# Kasli-SOC_ETH_PHY.net
KiCad netlist of a schematic drawn in Altium Designer
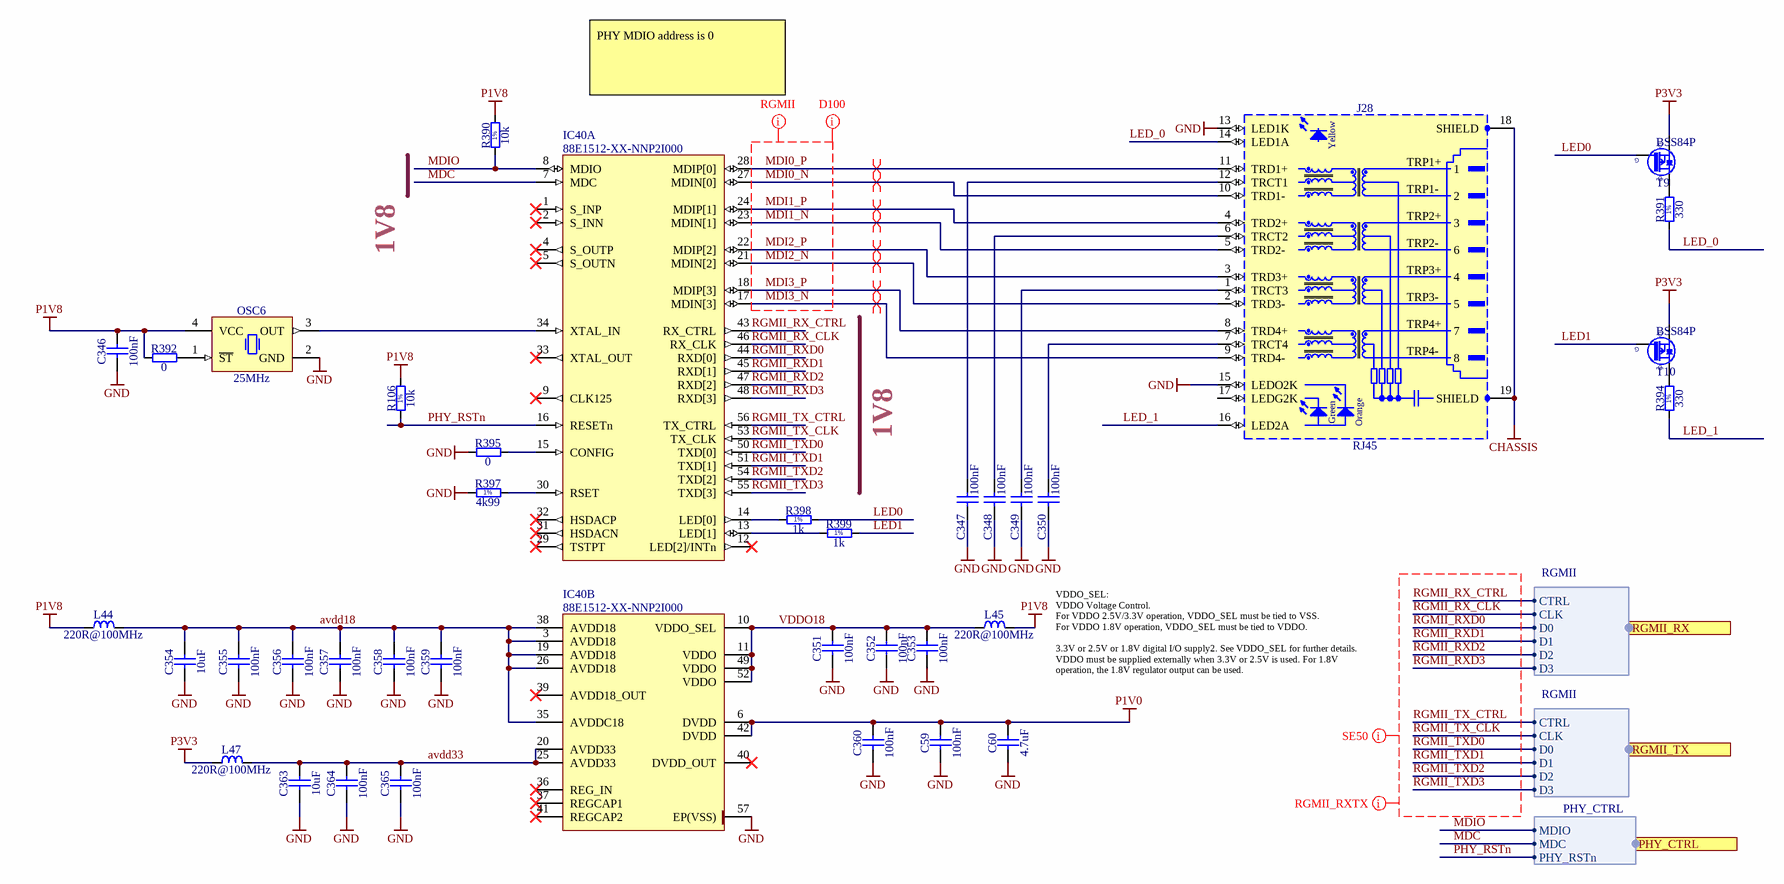
[diagram p0: Kasli-SOC_ETH_PHY.SchDoc]

(export (version "E")
  (design (tool "Eeschema 10.0.6"))
  (components
    (comp (ref "C59")
      (value "100nF")
      (footprint "CAPC0603X33N")
      (description "Non-polarised capacitor")
      (fields
        (field (name "PART NUMBER") "CC0201_100NF_6.3V_10%_X5R")
        (field (name "VOLTAGE") "6.3V")
        (field (name "AUTHOR") "CERN DEM JLC")
      )
      (libsource (lib "Capacitors") (part "Capacitor - non polarized"))
    )
    (comp (ref "C60")
      (value "4.7uF")
      (footprint "CAPC1709X95N")
      (description "Non-polarised capacitor")
      (fields
        (field (name "PART NUMBER") "CC0603_4.7UF_16V_10%_X5R")
        (field (name "VOLTAGE") "16V")
        (field (name "AUTHOR") "CERN DEM JLC")
      )
      (libsource (lib "Capacitors") (part "Capacitor - non polarized"))
    )
    (comp (ref "C346")
      (value "100nF")
      (footprint "CAPC1005X55N")
      (description "Non-polarised capacitor")
      (fields
        (field (name "PART NUMBER") "CC0402_100NF_16V_10%_X7R")
        (field (name "VOLTAGE") "16V")
        (field (name "AUTHOR") "CERN DEM JLC")
      )
      (libsource (lib "Capacitors") (part "Capacitor - non polarized"))
    )
    (comp (ref "C347")
      (value "100nF")
      (footprint "CAPC1005X55N")
      (description "Non-polarised capacitor")
      (fields
        (field (name "PART NUMBER") "CC0402_100NF_16V_10%_X7R")
        (field (name "VOLTAGE") "16V")
        (field (name "AUTHOR") "CERN DEM JLC")
      )
      (libsource (lib "Capacitors") (part "Capacitor - non polarized"))
    )
    (comp (ref "C348")
      (value "100nF")
      (footprint "CAPC1005X55N")
      (description "Non-polarised capacitor")
      (fields
        (field (name "PART NUMBER") "CC0402_100NF_16V_10%_X7R")
        (field (name "VOLTAGE") "16V")
        (field (name "AUTHOR") "CERN DEM JLC")
      )
      (libsource (lib "Capacitors") (part "Capacitor - non polarized"))
    )
    (comp (ref "C349")
      (value "100nF")
      (footprint "CAPC1005X55N")
      (description "Non-polarised capacitor")
      (fields
        (field (name "PART NUMBER") "CC0402_100NF_16V_10%_X7R")
        (field (name "VOLTAGE") "16V")
        (field (name "AUTHOR") "CERN DEM JLC")
      )
      (libsource (lib "Capacitors") (part "Capacitor - non polarized"))
    )
    (comp (ref "C350")
      (value "100nF")
      (footprint "CAPC1005X55N")
      (description "Non-polarised capacitor")
      (fields
        (field (name "PART NUMBER") "CC0402_100NF_16V_10%_X7R")
        (field (name "VOLTAGE") "16V")
        (field (name "AUTHOR") "CERN DEM JLC")
      )
      (libsource (lib "Capacitors") (part "Capacitor - non polarized"))
    )
    (comp (ref "C351")
      (value "100nF")
      (footprint "CAPC0603X33N")
      (description "Non-polarised capacitor")
      (fields
        (field (name "PART NUMBER") "CC0201_100NF_6.3V_10%_X5R")
        (field (name "VOLTAGE") "6.3V")
        (field (name "AUTHOR") "CERN DEM JLC")
      )
      (libsource (lib "Capacitors") (part "Capacitor - non polarized"))
    )
    (comp (ref "C352")
      (value "100nF")
      (footprint "CAPC0603X33N")
      (description "Non-polarised capacitor")
      (fields
        (field (name "PART NUMBER") "CC0201_100NF_6.3V_10%_X5R")
        (field (name "VOLTAGE") "6.3V")
        (field (name "AUTHOR") "CERN DEM JLC")
      )
      (libsource (lib "Capacitors") (part "Capacitor - non polarized"))
    )
    (comp (ref "C353")
      (value "100nF")
      (footprint "CAPC0603X33N")
      (description "Non-polarised capacitor")
      (fields
        (field (name "PART NUMBER") "CC0201_100NF_6.3V_10%_X5R")
        (field (name "VOLTAGE") "6.3V")
        (field (name "AUTHOR") "CERN DEM JLC")
      )
      (libsource (lib "Capacitors") (part "Capacitor - non polarized"))
    )
    (comp (ref "C354")
      (value "10uF")
      (footprint "CAPC1608X80N")
      (description "Non-polarised capacitor")
      (fields
        (field (name "PART NUMBER") "CC0603_10UF_16V_20%_X5R")
        (field (name "VOLTAGE") "16V")
        (field (name "AUTHOR") "CERN DEM MR")
      )
      (libsource (lib "Capacitors") (part "Capacitor - non polarized"))
    )
    (comp (ref "C355")
      (value "100nF")
      (footprint "CAPC0603X33N")
      (description "Non-polarised capacitor")
      (fields
        (field (name "PART NUMBER") "CC0201_100NF_6.3V_10%_X5R")
        (field (name "VOLTAGE") "6.3V")
        (field (name "AUTHOR") "CERN DEM JLC")
      )
      (libsource (lib "Capacitors") (part "Capacitor - non polarized"))
    )
    (comp (ref "C356")
      (value "100nF")
      (footprint "CAPC0603X33N")
      (description "Non-polarised capacitor")
      (fields
        (field (name "PART NUMBER") "CC0201_100NF_6.3V_10%_X5R")
        (field (name "VOLTAGE") "6.3V")
        (field (name "AUTHOR") "CERN DEM JLC")
      )
      (libsource (lib "Capacitors") (part "Capacitor - non polarized"))
    )
    (comp (ref "C357")
      (value "100nF")
      (footprint "CAPC0603X33N")
      (description "Non-polarised capacitor")
      (fields
        (field (name "PART NUMBER") "CC0201_100NF_6.3V_10%_X5R")
        (field (name "VOLTAGE") "6.3V")
        (field (name "AUTHOR") "CERN DEM JLC")
      )
      (libsource (lib "Capacitors") (part "Capacitor - non polarized"))
    )
    (comp (ref "C358")
      (value "100nF")
      (footprint "CAPC0603X33N")
      (description "Non-polarised capacitor")
      (fields
        (field (name "PART NUMBER") "CC0201_100NF_6.3V_10%_X5R")
        (field (name "VOLTAGE") "6.3V")
        (field (name "AUTHOR") "CERN DEM JLC")
      )
      (libsource (lib "Capacitors") (part "Capacitor - non polarized"))
    )
    (comp (ref "C359")
      (value "100nF")
      (footprint "CAPC0603X33N")
      (description "Non-polarised capacitor")
      (fields
        (field (name "PART NUMBER") "CC0201_100NF_6.3V_10%_X5R")
        (field (name "VOLTAGE") "6.3V")
        (field (name "AUTHOR") "CERN DEM JLC")
      )
      (libsource (lib "Capacitors") (part "Capacitor - non polarized"))
    )
    (comp (ref "C360")
      (value "100nF")
      (footprint "CAPC0603X33N")
      (description "Non-polarised capacitor")
      (fields
        (field (name "PART NUMBER") "CC0201_100NF_6.3V_10%_X5R")
        (field (name "VOLTAGE") "6.3V")
        (field (name "AUTHOR") "CERN DEM JLC")
      )
      (libsource (lib "Capacitors") (part "Capacitor - non polarized"))
    )
    (comp (ref "C363")
      (value "10uF")
      (footprint "CAPC1608X80N")
      (description "Non-polarised capacitor")
      (fields
        (field (name "PART NUMBER") "CC0603_10UF_16V_20%_X5R")
        (field (name "VOLTAGE") "16V")
        (field (name "AUTHOR") "CERN DEM MR")
      )
      (libsource (lib "Capacitors") (part "Capacitor - non polarized"))
    )
    (comp (ref "C364")
      (value "100nF")
      (footprint "CAPC0603X33N")
      (description "Non-polarised capacitor")
      (fields
        (field (name "PART NUMBER") "CC0201_100NF_6.3V_10%_X5R")
        (field (name "VOLTAGE") "6.3V")
        (field (name "AUTHOR") "CERN DEM JLC")
      )
      (libsource (lib "Capacitors") (part "Capacitor - non polarized"))
    )
    (comp (ref "C365")
      (value "100nF")
      (footprint "CAPC0603X33N")
      (description "Non-polarised capacitor")
      (fields
        (field (name "PART NUMBER") "CC0201_100NF_6.3V_10%_X5R")
        (field (name "VOLTAGE") "6.3V")
        (field (name "AUTHOR") "CERN DEM JLC")
      )
      (libsource (lib "Capacitors") (part "Capacitor - non polarized"))
    )
    (comp (ref "IC40")
      (value "88E1512-XX-NNP2I000")
      (footprint "QFN50P800X800X100-57N-S437")
      (description "Alaska Integrated 10/100/1000 Mbps Energy Efficient Ethernet Transceiver")
      (fields (field (name "MANUFACTURER") "MARVELL  TECHNOLOGY") (field (name "AUTHOR") "CERN DEM JLC"))
      (libsource (lib "ICs And Semiconductors") (part "88E1512-XX-NNP2I000"))
    )
    (comp (ref "J28")
      (value "RJ45")
      (footprint "BEL_L829-1J1T-43")
      (description "1 Port, RJ45, Gigabit Ethernet, MagJack Connector Module With Yellow And Green/Orange LEDs")
      (fields
        (field (name "PART NUMBER") "BELFUSE_L829-1J1T-43")
        (field (name "MANUFACTURER") "BEL MAGNETIC SOLUTIONS")
        (field (name "AUTHOR") "CERN DEM JLC")
      )
      (libsource (lib "Miscellaneous") (part "BELFUSE_L829-1J1T-43"))
    )
    (comp (ref "L44")
      (value "220R@100MHz")
      (footprint "INDC2012X105N")
      (description "Inductor")
      (fields
        (field (name "PART NUMBER") "IND0805_MURATA_BLM21PG221SN1D")
        (field (name "POWER") "2A")
        (field (name "AUTHOR") "CERN DEM JLC")
      )
      (libsource (lib "Inductors & Transformers") (part "Inductor"))
    )
    (comp (ref "L45")
      (value "220R@100MHz")
      (footprint "INDC2012X105N")
      (description "Inductor")
      (fields
        (field (name "PART NUMBER") "IND0805_MURATA_BLM21PG221SN1D")
        (field (name "POWER") "2A")
        (field (name "AUTHOR") "CERN DEM JLC")
      )
      (libsource (lib "Inductors & Transformers") (part "Inductor"))
    )
    (comp (ref "L47")
      (value "220R@100MHz")
      (footprint "INDC2012X105N")
      (description "Inductor")
      (fields
        (field (name "PART NUMBER") "IND0805_MURATA_BLM21PG221SN1D")
        (field (name "POWER") "2A")
        (field (name "AUTHOR") "CERN DEM JLC")
      )
      (libsource (lib "Inductors & Transformers") (part "Inductor"))
    )
    (comp (ref "OSC6")
      (value "25MHz")
      (footprint "OSC_MICREL_2520")
      (description "Oscillator 4 pins 1=\\ST 2=GND 3=OUT 4=VCC")
      (fields
        (field (name "PART NUMBER") "OSC_25MHZ_MICREL_DSC1001DI5-025.0000T")
        (field (name "MANUFACTURER") "MICREL")
        (field (name "AUTHOR") "CERN DEM JLC")
      )
      (libsource (lib "ICs And Semiconductors") (part "Oscillator 1ST 2GND 3OUT 4VCC"))
    )
    (comp (ref "R106")
      (value "10k")
      (footprint "RESC1005X40N")
      (description "Resistor - 1%")
      (fields
        (field (name "PART NUMBER") "R0402_10K_1%_0.0625W_100PPM")
        (field (name "POWER") "0.0625W")
        (field (name "AUTHOR") "CERN DEM JLC")
      )
      (libsource (lib "Resistors") (part "Resistor - 1%"))
    )
    (comp (ref "R390")
      (value "10k")
      (footprint "RESC1005X40N")
      (description "Resistor - 1%")
      (fields
        (field (name "PART NUMBER") "R0402_10K_1%_0.0625W_100PPM")
        (field (name "POWER") "0.0625W")
        (field (name "AUTHOR") "CERN DEM JLC")
      )
      (libsource (lib "Resistors") (part "Resistor - 1%"))
    )
    (comp (ref "R391")
      (value "330")
      (footprint "RESC1005X40N")
      (description "Resistor - 1%")
      (fields
        (field (name "PART NUMBER") "R0402_330R_1%_0.0625W_100PPM")
        (field (name "POWER") "0.0625W")
        (field (name "AUTHOR") "CERN DEM JLC")
      )
      (libsource (lib "Resistors") (part "Resistor - 1%"))
    )
    (comp (ref "R392")
      (value "0")
      (footprint "RESC1005X40N")
      (description "Resistor")
      (fields
        (field (name "PART NUMBER") "R0402_0R_JUMPER")
        (field (name "MANUFACTURER") "GENERIC")
        (field (name "AUTHOR") "CERN DEM JLC")
      )
      (libsource (lib "Resistors") (part "Resistor"))
    )
    (comp (ref "R394")
      (value "330")
      (footprint "RESC1005X40N")
      (description "Resistor - 1%")
      (fields
        (field (name "PART NUMBER") "R0402_330R_1%_0.0625W_100PPM")
        (field (name "POWER") "0.0625W")
        (field (name "AUTHOR") "CERN DEM JLC")
      )
      (libsource (lib "Resistors") (part "Resistor - 1%"))
    )
    (comp (ref "R395")
      (value "0")
      (footprint "RESC1005X40N")
      (description "Resistor")
      (fields
        (field (name "PART NUMBER") "R0402_0R_JUMPER")
        (field (name "MANUFACTURER") "GENERIC")
        (field (name "AUTHOR") "CERN DEM JLC")
      )
      (libsource (lib "Resistors") (part "Resistor"))
    )
    (comp (ref "R397")
      (value "4k99")
      (footprint "RESC1608X55N")
      (description "Resistor - 1%")
      (fields
        (field (name "PART NUMBER") "R0603_4K99_1%_0.063W_50PPM")
        (field (name "POWER") "0.063W")
        (field (name "AUTHOR") "CERN DEM JLC")
      )
      (libsource (lib "Resistors") (part "Resistor - 1%"))
    )
    (comp (ref "R398")
      (value "1k")
      (footprint "RESC1005X40N")
      (description "Resistor - 1%")
      (fields
        (field (name "PART NUMBER") "R0402_1K_1%_0.0625W_100PPM")
        (field (name "POWER") "0.0625W")
        (field (name "AUTHOR") "CERN DEM JLC")
      )
      (libsource (lib "Resistors") (part "Resistor - 1%"))
    )
    (comp (ref "R399")
      (value "1k")
      (footprint "RESC1005X40N")
      (description "Resistor - 1%")
      (fields
        (field (name "PART NUMBER") "R0402_1K_1%_0.0625W_100PPM")
        (field (name "POWER") "0.0625W")
        (field (name "AUTHOR") "CERN DEM JLC")
      )
      (libsource (lib "Resistors") (part "Resistor - 1%"))
    )
    (comp (ref "T9")
      (value "BSS84P")
      (footprint "SOT95P240X110-3N")
      (description "P-CHANNEL MOSFET WITH DIODE")
      (fields (field (name "MANUFACTURER") "INFINEON") (field (name "AUTHOR") "CERN DEM JLC"))
      (libsource (lib "ICs And Semiconductors") (part "P-MOSFET-D 1G 2S 3D"))
    )
    (comp (ref "T10")
      (value "BSS84P")
      (footprint "SOT95P240X110-3N")
      (description "P-CHANNEL MOSFET WITH DIODE")
      (fields (field (name "MANUFACTURER") "INFINEON") (field (name "AUTHOR") "CERN DEM JLC"))
      (libsource (lib "ICs And Semiconductors") (part "P-MOSFET-D 1G 2S 3D"))
    )
  )
  (nets
    (net (code "3") (name "/LED0") (class "Default")
      (node (ref "R398") (pin "2") (pinfunction "2_2") (pintype "passive"))
      (node (ref "T9") (pin "1") (pinfunction "G_1") (pintype "passive"))
    )
    (net (code "4") (name "/LED1") (class "Default")
      (node (ref "R399") (pin "2") (pinfunction "2_2") (pintype "passive"))
      (node (ref "T10") (pin "1") (pinfunction "G_1") (pintype "passive"))
    )
    (net (code "5") (name "/LED_0") (class "Default")
      (node (ref "J28") (pin "14") (pinfunction "LED1A_14") (pintype "bidirectional"))
      (node (ref "R391") (pin "1") (pinfunction "1_1") (pintype "passive"))
    )
    (net (code "6") (name "/LED_1") (class "Default")
      (node (ref "J28") (pin "16") (pinfunction "LED2A_16") (pintype "bidirectional"))
      (node (ref "R394") (pin "1") (pinfunction "1_1") (pintype "passive"))
    )
    (net (code "7") (name "/MDC") (class "Default")
      (node (ref "IC40") (pin "7") (pinfunction "MDC_7") (pintype "input"))
    )
    (net (code "8") (name "/MDI0_N") (class "Default")
      (node (ref "IC40") (pin "27") (pinfunction "MDIN[0]_27") (pintype "bidirectional"))
      (node (ref "J28") (pin "10") (pinfunction "TRD1-_10") (pintype "bidirectional"))
    )
    (net (code "9") (name "/MDI0_P") (class "Default")
      (node (ref "IC40") (pin "28") (pinfunction "MDIP[0]_28") (pintype "bidirectional"))
      (node (ref "J28") (pin "11") (pinfunction "TRD1+_11") (pintype "bidirectional"))
    )
    (net (code "10") (name "/MDI1_N") (class "Default")
      (node (ref "IC40") (pin "23") (pinfunction "MDIN[1]_23") (pintype "bidirectional"))
      (node (ref "J28") (pin "5") (pinfunction "TRD2-_5") (pintype "bidirectional"))
    )
    (net (code "11") (name "/MDI1_P") (class "Default")
      (node (ref "IC40") (pin "24") (pinfunction "MDIP[1]_24") (pintype "bidirectional"))
      (node (ref "J28") (pin "4") (pinfunction "TRD2+_4") (pintype "bidirectional"))
    )
    (net (code "12") (name "/MDI2_N") (class "Default")
      (node (ref "IC40") (pin "21") (pinfunction "MDIN[2]_21") (pintype "bidirectional"))
      (node (ref "J28") (pin "2") (pinfunction "TRD3-_2") (pintype "bidirectional"))
    )
    (net (code "13") (name "/MDI2_P") (class "Default")
      (node (ref "IC40") (pin "22") (pinfunction "MDIP[2]_22") (pintype "bidirectional"))
      (node (ref "J28") (pin "3") (pinfunction "TRD3+_3") (pintype "bidirectional"))
    )
    (net (code "14") (name "/MDI3_N") (class "Default")
      (node (ref "IC40") (pin "17") (pinfunction "MDIN[3]_17") (pintype "bidirectional"))
      (node (ref "J28") (pin "9") (pinfunction "TRD4-_9") (pintype "bidirectional"))
    )
    (net (code "15") (name "/MDI3_P") (class "Default")
      (node (ref "IC40") (pin "18") (pinfunction "MDIP[3]_18") (pintype "bidirectional"))
      (node (ref "J28") (pin "8") (pinfunction "TRD4+_8") (pintype "bidirectional"))
    )
    (net (code "16") (name "/MDIO") (class "Default")
      (node (ref "IC40") (pin "8") (pinfunction "MDIO_8") (pintype "bidirectional"))
      (node (ref "R390") (pin "1") (pinfunction "1_1") (pintype "passive"))
    )
    (net (code "17") (name "/PHY_RSTn") (class "Default")
      (node (ref "IC40") (pin "16") (pinfunction "RESETn_16") (pintype "input"))
      (node (ref "R106") (pin "1") (pinfunction "1_1") (pintype "passive"))
    )
    (net (code "18") (name "/RGMII_RXD0") (class "Default")
      (node (ref "IC40") (pin "44") (pinfunction "RXD[0]_44") (pintype "output"))
    )
    (net (code "19") (name "/RGMII_RXD1") (class "Default")
      (node (ref "IC40") (pin "45") (pinfunction "RXD[1]_45") (pintype "output"))
    )
    (net (code "20") (name "/RGMII_RXD2") (class "Default")
      (node (ref "IC40") (pin "47") (pinfunction "RXD[2]_47") (pintype "output"))
    )
    (net (code "21") (name "/RGMII_RXD3") (class "Default")
      (node (ref "IC40") (pin "48") (pinfunction "RXD[3]_48") (pintype "output"))
    )
    (net (code "22") (name "/RGMII_RX_CLK") (class "Default")
      (node (ref "IC40") (pin "46") (pinfunction "RX_CLK_46") (pintype "output"))
    )
    (net (code "23") (name "/RGMII_RX_CTRL") (class "Default")
      (node (ref "IC40") (pin "43") (pinfunction "RX_CTRL_43") (pintype "output"))
    )
    (net (code "24") (name "/RGMII_TXD0") (class "Default")
      (node (ref "IC40") (pin "50") (pinfunction "TXD[0]_50") (pintype "input"))
    )
    (net (code "25") (name "/RGMII_TXD1") (class "Default")
      (node (ref "IC40") (pin "51") (pinfunction "TXD[1]_51") (pintype "input"))
    )
    (net (code "26") (name "/RGMII_TXD2") (class "Default")
      (node (ref "IC40") (pin "54") (pinfunction "TXD[2]_54") (pintype "input"))
    )
    (net (code "27") (name "/RGMII_TXD3") (class "Default")
      (node (ref "IC40") (pin "55") (pinfunction "TXD[3]_55") (pintype "input"))
    )
    (net (code "28") (name "/RGMII_TX_CLK") (class "Default")
      (node (ref "IC40") (pin "53") (pinfunction "TX_CLK_53") (pintype "input"))
    )
    (net (code "29") (name "/RGMII_TX_CTRL") (class "Default")
      (node (ref "IC40") (pin "56") (pinfunction "TX_CTRL_56") (pintype "input"))
    )
    (net (code "30") (name "/VDDO18") (class "Default")
      (node (ref "C351") (pin "2") (pinfunction "2_2") (pintype "passive"))
      (node (ref "C352") (pin "2") (pinfunction "2_2") (pintype "passive"))
      (node (ref "C353") (pin "2") (pinfunction "2_2") (pintype "passive"))
      (node (ref "IC40") (pin "10") (pinfunction "VDDO_SEL_10") (pintype "power_in"))
      (node (ref "IC40") (pin "11") (pinfunction "VDDO_11") (pintype "power_in"))
      (node (ref "IC40") (pin "49") (pinfunction "VDDO_49") (pintype "power_in"))
      (node (ref "IC40") (pin "52") (pinfunction "VDDO_52") (pintype "power_in"))
      (node (ref "L45") (pin "1") (pinfunction "1_1") (pintype "passive"))
    )
    (net (code "31") (name "/avdd18") (class "Default")
      (node (ref "C354") (pin "2") (pinfunction "2_2") (pintype "passive"))
      (node (ref "C355") (pin "2") (pinfunction "2_2") (pintype "passive"))
      (node (ref "C356") (pin "2") (pinfunction "2_2") (pintype "passive"))
      (node (ref "C357") (pin "2") (pinfunction "2_2") (pintype "passive"))
      (node (ref "C358") (pin "2") (pinfunction "2_2") (pintype "passive"))
      (node (ref "C359") (pin "2") (pinfunction "2_2") (pintype "passive"))
      (node (ref "IC40") (pin "19") (pinfunction "AVDD18_19") (pintype "power_in"))
      (node (ref "IC40") (pin "26") (pinfunction "AVDD18_26") (pintype "power_in"))
      (node (ref "IC40") (pin "3") (pinfunction "AVDD18_3") (pintype "power_in"))
      (node (ref "IC40") (pin "35") (pinfunction "AVDDC18_35") (pintype "power_in"))
      (node (ref "IC40") (pin "38") (pinfunction "AVDD18_38") (pintype "power_in"))
      (node (ref "L44") (pin "2") (pinfunction "2_2") (pintype "passive"))
    )
    (net (code "32") (name "/avdd33") (class "Default")
      (node (ref "C363") (pin "2") (pinfunction "2_2") (pintype "passive"))
      (node (ref "C364") (pin "2") (pinfunction "2_2") (pintype "passive"))
      (node (ref "C365") (pin "2") (pinfunction "2_2") (pintype "passive"))
      (node (ref "IC40") (pin "20") (pinfunction "AVDD33_20") (pintype "power_in"))
      (node (ref "IC40") (pin "25") (pinfunction "AVDD33_25") (pintype "power_in"))
      (node (ref "L47") (pin "2") (pinfunction "2_2") (pintype "passive"))
    )
    (net (code "35") (name "CHASSIS") (class "Default")
      (node (ref "J28") (pin "18") (pinfunction "SHIELD_18") (pintype "power_in"))
      (node (ref "J28") (pin "19") (pinfunction "SHIELD_19") (pintype "power_in"))
    )
    (net (code "36") (name "GND") (class "Default")
      (node (ref "C346") (pin "1") (pinfunction "1_1") (pintype "passive"))
      (node (ref "C347") (pin "1") (pinfunction "1_1") (pintype "passive"))
      (node (ref "C348") (pin "1") (pinfunction "1_1") (pintype "passive"))
      (node (ref "C349") (pin "1") (pinfunction "1_1") (pintype "passive"))
      (node (ref "C350") (pin "1") (pinfunction "1_1") (pintype "passive"))
      (node (ref "C351") (pin "1") (pinfunction "1_1") (pintype "passive"))
      (node (ref "C352") (pin "1") (pinfunction "1_1") (pintype "passive"))
      (node (ref "C353") (pin "1") (pinfunction "1_1") (pintype "passive"))
      (node (ref "C354") (pin "1") (pinfunction "1_1") (pintype "passive"))
      (node (ref "C355") (pin "1") (pinfunction "1_1") (pintype "passive"))
      (node (ref "C356") (pin "1") (pinfunction "1_1") (pintype "passive"))
      (node (ref "C357") (pin "1") (pinfunction "1_1") (pintype "passive"))
      (node (ref "C358") (pin "1") (pinfunction "1_1") (pintype "passive"))
      (node (ref "C359") (pin "1") (pinfunction "1_1") (pintype "passive"))
      (node (ref "C360") (pin "1") (pinfunction "1_1") (pintype "passive"))
      (node (ref "C363") (pin "1") (pinfunction "1_1") (pintype "passive"))
      (node (ref "C364") (pin "1") (pinfunction "1_1") (pintype "passive"))
      (node (ref "C365") (pin "1") (pinfunction "1_1") (pintype "passive"))
      (node (ref "C59") (pin "1") (pinfunction "1_1") (pintype "passive"))
      (node (ref "C60") (pin "1") (pinfunction "1_1") (pintype "passive"))
      (node (ref "IC40") (pin "57") (pinfunction "EP(VSS)_57") (pintype "power_in"))
      (node (ref "J28") (pin "13") (pinfunction "LED1K_13") (pintype "bidirectional"))
      (node (ref "J28") (pin "15") (pinfunction "LEDO2K_15") (pintype "bidirectional"))
      (node (ref "OSC6") (pin "2") (pinfunction "GND_2") (pintype "power_in"))
      (node (ref "R395") (pin "1") (pinfunction "1_1") (pintype "passive"))
      (node (ref "R397") (pin "1") (pinfunction "1_1") (pintype "passive"))
    )
    (net (code "37") (name "Net-(IC40A-CONFIG)") (class "Default")
      (node (ref "IC40") (pin "15") (pinfunction "CONFIG_15") (pintype "input"))
      (node (ref "R395") (pin "2") (pinfunction "2_2") (pintype "passive"))
    )
    (net (code "38") (name "Net-(IC40A-LED[0])") (class "Default")
      (node (ref "IC40") (pin "14") (pinfunction "LED[0]_14") (pintype "output"))
      (node (ref "R398") (pin "1") (pinfunction "1_1") (pintype "passive"))
    )
    (net (code "39") (name "Net-(IC40A-LED[1])") (class "Default")
      (node (ref "IC40") (pin "13") (pinfunction "LED[1]_13") (pintype "bidirectional"))
      (node (ref "R399") (pin "1") (pinfunction "1_1") (pintype "passive"))
    )
    (net (code "40") (name "Net-(IC40A-RSET)") (class "Default")
      (node (ref "IC40") (pin "30") (pinfunction "RSET_30") (pintype "input"))
      (node (ref "R397") (pin "2") (pinfunction "2_2") (pintype "passive"))
    )
    (net (code "41") (name "Net-(IC40A-XTAL_IN)") (class "Default")
      (node (ref "IC40") (pin "34") (pinfunction "XTAL_IN_34") (pintype "input"))
      (node (ref "OSC6") (pin "3") (pinfunction "OUT_3") (pintype "output"))
    )
    (net (code "42") (name "Net-(J28-TRCT1)") (class "Default")
      (node (ref "C347") (pin "2") (pinfunction "2_2") (pintype "passive"))
      (node (ref "J28") (pin "12") (pinfunction "TRCT1_12") (pintype "bidirectional"))
    )
    (net (code "43") (name "Net-(J28-TRCT2)") (class "Default")
      (node (ref "C348") (pin "2") (pinfunction "2_2") (pintype "passive"))
      (node (ref "J28") (pin "6") (pinfunction "TRCT2_6") (pintype "bidirectional"))
    )
    (net (code "44") (name "Net-(J28-TRCT3)") (class "Default")
      (node (ref "C349") (pin "2") (pinfunction "2_2") (pintype "passive"))
      (node (ref "J28") (pin "1") (pinfunction "TRCT3_1") (pintype "bidirectional"))
    )
    (net (code "45") (name "Net-(J28-TRCT4)") (class "Default")
      (node (ref "C350") (pin "2") (pinfunction "2_2") (pintype "passive"))
      (node (ref "J28") (pin "7") (pinfunction "TRCT4_7") (pintype "bidirectional"))
    )
    (net (code "46") (name "Net-(OSC6-ST)") (class "Default")
      (node (ref "OSC6") (pin "1") (pinfunction "ST_1") (pintype "input"))
      (node (ref "R392") (pin "2") (pinfunction "2_2") (pintype "passive"))
    )
    (net (code "47") (name "Net-(T9-D)") (class "Default")
      (node (ref "R391") (pin "2") (pinfunction "2_2") (pintype "passive"))
      (node (ref "T9") (pin "3") (pinfunction "D_3") (pintype "passive"))
    )
    (net (code "48") (name "Net-(T10-D)") (class "Default")
      (node (ref "R394") (pin "2") (pinfunction "2_2") (pintype "passive"))
      (node (ref "T10") (pin "3") (pinfunction "D_3") (pintype "passive"))
    )
    (net (code "49") (name "P1V0") (class "Default")
      (node (ref "C360") (pin "2") (pinfunction "2_2") (pintype "passive"))
      (node (ref "C59") (pin "2") (pinfunction "2_2") (pintype "passive"))
      (node (ref "C60") (pin "2") (pinfunction "2_2") (pintype "passive"))
      (node (ref "IC40") (pin "42") (pinfunction "DVDD_42") (pintype "power_in"))
      (node (ref "IC40") (pin "6") (pinfunction "DVDD_6") (pintype "power_in"))
    )
    (net (code "50") (name "P1V8") (class "Default")
      (node (ref "C346") (pin "2") (pinfunction "2_2") (pintype "passive"))
      (node (ref "L44") (pin "1") (pinfunction "1_1") (pintype "passive"))
      (node (ref "L45") (pin "2") (pinfunction "2_2") (pintype "passive"))
      (node (ref "OSC6") (pin "4") (pinfunction "VCC_4") (pintype "power_in"))
      (node (ref "R106") (pin "2") (pinfunction "2_2") (pintype "passive"))
      (node (ref "R390") (pin "2") (pinfunction "2_2") (pintype "passive"))
      (node (ref "R392") (pin "1") (pinfunction "1_1") (pintype "passive"))
    )
    (net (code "51") (name "P3V3") (class "Default")
      (node (ref "L47") (pin "1") (pinfunction "1_1") (pintype "passive"))
      (node (ref "T10") (pin "2") (pinfunction "S_2") (pintype "passive"))
      (node (ref "T9") (pin "2") (pinfunction "S_2") (pintype "passive"))
    )
    (net (code "52") (name "unconnected-(IC40A-CLK125-Pad9)") (class "Default")
      (node (ref "IC40") (pin "9") (pinfunction "CLK125_9") (pintype "output+no_connect"))
    )
    (net (code "53") (name "unconnected-(IC40A-HSDACN-Pad31)") (class "Default")
      (node (ref "IC40") (pin "31") (pinfunction "HSDACN_31") (pintype "output+no_connect"))
    )
    (net (code "54") (name "unconnected-(IC40A-HSDACP-Pad32)") (class "Default")
      (node (ref "IC40") (pin "32") (pinfunction "HSDACP_32") (pintype "output+no_connect"))
    )
    (net (code "55") (name "unconnected-(IC40A-LED[2]{slash}INTn-Pad12)") (class "Default")
      (node (ref "IC40") (pin "12") (pinfunction "LED[2]/INTn_12") (pintype "output+no_connect"))
    )
    (net (code "56") (name "unconnected-(IC40A-S_INN-Pad2)") (class "Default")
      (node (ref "IC40") (pin "2") (pinfunction "S_INN_2") (pintype "input+no_connect"))
    )
    (net (code "57") (name "unconnected-(IC40A-S_INP-Pad1)") (class "Default")
      (node (ref "IC40") (pin "1") (pinfunction "S_INP_1") (pintype "input+no_connect"))
    )
    (net (code "58") (name "unconnected-(IC40A-S_OUTN-Pad5)") (class "Default")
      (node (ref "IC40") (pin "5") (pinfunction "S_OUTN_5") (pintype "output+no_connect"))
    )
    (net (code "59") (name "unconnected-(IC40A-S_OUTP-Pad4)") (class "Default")
      (node (ref "IC40") (pin "4") (pinfunction "S_OUTP_4") (pintype "output+no_connect"))
    )
    (net (code "60") (name "unconnected-(IC40A-TSTPT-Pad29)") (class "Default")
      (node (ref "IC40") (pin "29") (pinfunction "TSTPT_29") (pintype "output+no_connect"))
    )
    (net (code "61") (name "unconnected-(IC40A-XTAL_OUT-Pad33)") (class "Default")
      (node (ref "IC40") (pin "33") (pinfunction "XTAL_OUT_33") (pintype "output+no_connect"))
    )
    (net (code "62") (name "unconnected-(IC40B-AVDD18_OUT-Pad39)") (class "Default")
      (node (ref "IC40") (pin "39") (pinfunction "AVDD18_OUT_39") (pintype "power_in+no_connect"))
    )
    (net (code "63") (name "unconnected-(IC40B-DVDD_OUT-Pad40)") (class "Default")
      (node (ref "IC40") (pin "40") (pinfunction "DVDD_OUT_40") (pintype "power_in+no_connect"))
    )
    (net (code "64") (name "unconnected-(IC40B-REGCAP1-Pad37)") (class "Default")
      (node (ref "IC40") (pin "37") (pinfunction "REGCAP1_37") (pintype "passive+no_connect"))
    )
    (net (code "65") (name "unconnected-(IC40B-REGCAP2-Pad41)") (class "Default")
      (node (ref "IC40") (pin "41") (pinfunction "REGCAP2_41") (pintype "passive+no_connect"))
    )
    (net (code "66") (name "unconnected-(IC40B-REG_IN-Pad36)") (class "Default")
      (node (ref "IC40") (pin "36") (pinfunction "REG_IN_36") (pintype "power_in+no_connect"))
    )
    (net (code "67") (name "unconnected-(J28-LEDG2K-Pad17)") (class "Default")
      (node (ref "J28") (pin "17") (pinfunction "LEDG2K_17") (pintype "bidirectional"))
    )
  )
)
